# 1025-A.net
KiCad netlist of a schematic drawn in Altium Designer
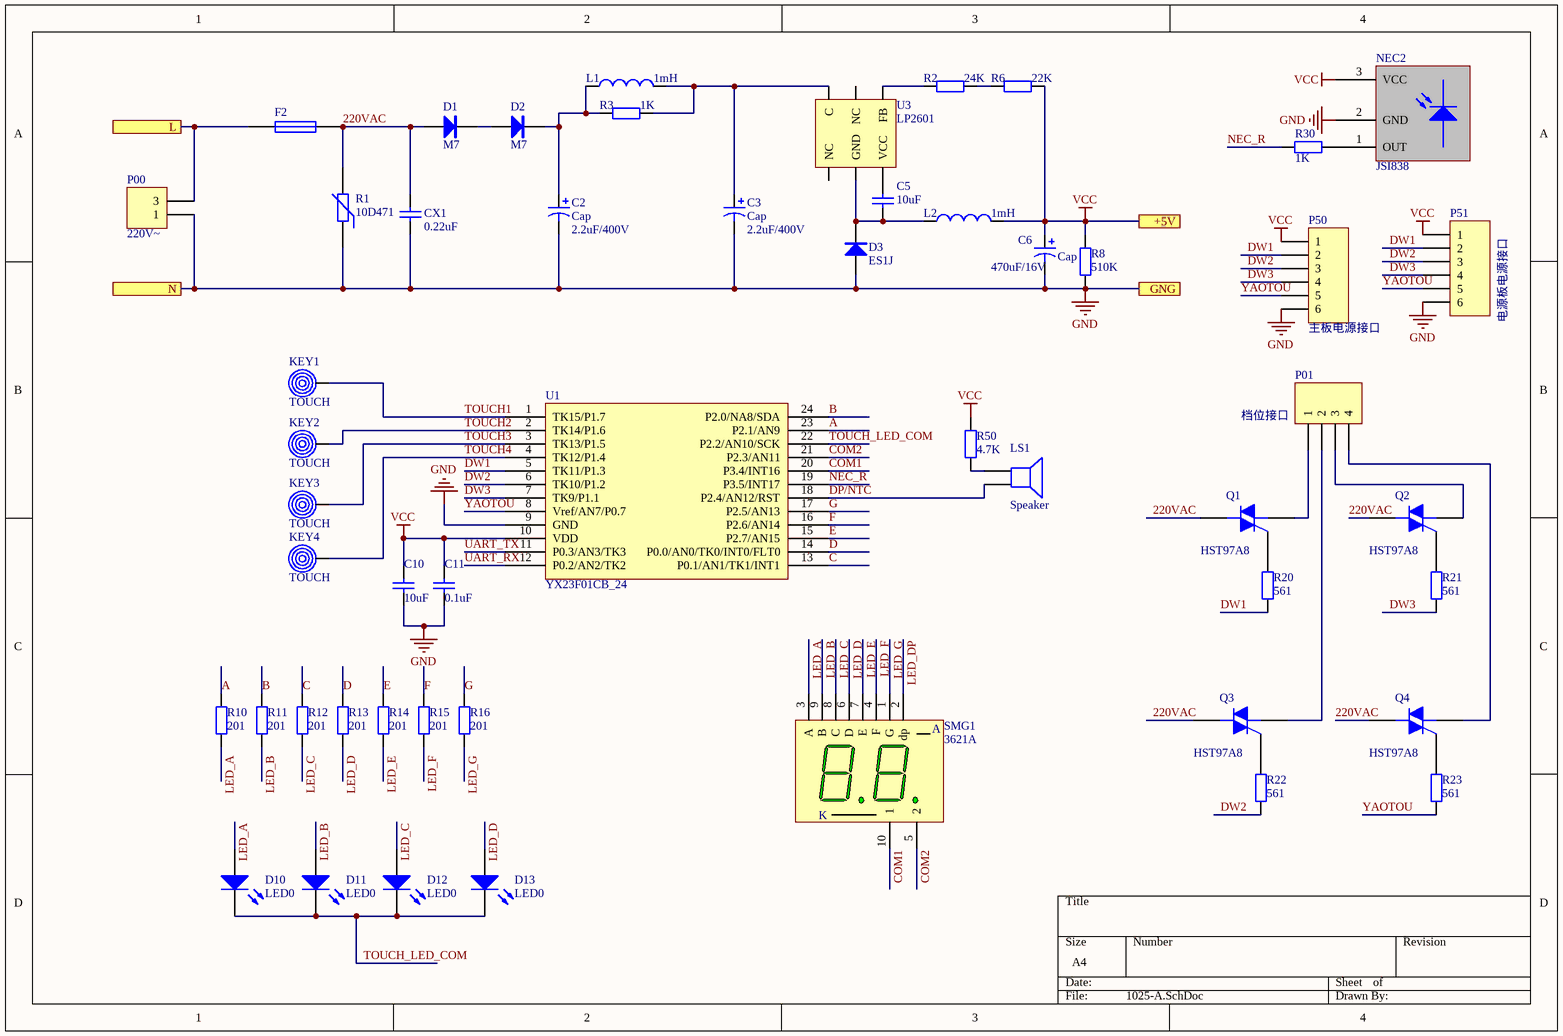
[diagram p0: 1025-A.SchDoc]

(export (version "E")
  (design (tool "Eeschema 10.0.6"))
  (components
    (comp (ref "C2")
      (value "Cap")
      (footprint "CAE8-3.05")
      (description "Polarized Capacitor (Radial)")
      (fields (field (name "ALTIUM_VALUE") "2.2uF/400V") (field (name "PUBLISHER") "Altium Limited"))
      (libsource (lib "Miscellaneous Devices") (part "Cap Pol1"))
    )
    (comp (ref "C3")
      (value "Cap")
      (footprint "CAE8-3.05")
      (description "Polarized Capacitor (Radial)")
      (fields (field (name "ALTIUM_VALUE") "2.2uF/400V") (field (name "PUBLISHER") "Altium Limited"))
      (libsource (lib "Miscellaneous Devices") (part "Cap Pol1"))
    )
    (comp (ref "C5")
      (value "10uF")
      (footprint "C 1206_M")
      (description "Capacitor")
      (fields (field (name "Comment") "Cap") (field (name "PUBLISHER") "Altium Limited"))
      (libsource (lib "Miscellaneous Devices") (part "Cap"))
    )
    (comp (ref "C6")
      (value "Cap")
      (footprint "CAE8-3.05")
      (description "Polarized Capacitor (Radial)")
      (fields (field (name "ALTIUM_VALUE") "470uF/16V") (field (name "PUBLISHER") "Altium Limited"))
      (libsource (lib "Miscellaneous Devices") (part "Cap Pol1"))
    )
    (comp (ref "C10")
      (value "10uF")
      (footprint "C 0805_L")
      (description "Capacitor")
      (fields (field (name "Comment") "Cap") (field (name "PUBLISHER") "Altium Limited"))
      (libsource (lib "Miscellaneous Devices") (part "Cap"))
    )
    (comp (ref "C11")
      (value "0.1uF")
      (footprint "C 0603_L")
      (description "Capacitor")
      (fields (field (name "Comment") "Cap") (field (name "PUBLISHER") "Altium Limited"))
      (libsource (lib "Miscellaneous Devices") (part "Cap"))
    )
    (comp (ref "CX1")
      (value "0.22uF")
      (footprint "CX2-13*5-10")
      (description "安规Capacitor")
      (fields (field (name "Comment") "安规电容") (field (name "PUBLISHER") "Altium Limited"))
      (libsource (lib "Miscellaneous Devices") (part "Cap"))
    )
    (comp (ref "D1")
      (value "M7")
      (footprint "D3528")
      (description "整流二极管")
      (fields (field (name "版权归属") "封装库来自淘宝 ID：黄晶宝石"))
      (libsource (lib "二极管-整流桥") (part "M7"))
    )
    (comp (ref "D2")
      (value "M7")
      (footprint "D3528")
      (description "整流二极管")
      (fields (field (name "版权归属") "封装库来自淘宝 ID：黄晶宝石"))
      (libsource (lib "二极管-整流桥") (part "M7"))
    )
    (comp (ref "D3")
      (value "ES1J")
      (footprint "D3528")
      (description "快速二极管")
      (fields (field (name "版权归属") "封装库来自淘宝 ID：黄晶宝石"))
      (libsource (lib "二极管-整流桥") (part "M7"))
    )
    (comp (ref "D10")
      (value "LED0")
      (footprint "LED 0805W")
      (description "Typical INFRARED GaAs LED")
      (fields (field (name "PUBLISHER") "Altium Limited"))
      (libsource (lib "Miscellaneous Devices") (part "LED0"))
    )
    (comp (ref "D11")
      (value "LED0")
      (footprint "LED 0805W")
      (description "Typical INFRARED GaAs LED")
      (fields (field (name "PUBLISHER") "Altium Limited"))
      (libsource (lib "Miscellaneous Devices") (part "LED0"))
    )
    (comp (ref "D12")
      (value "LED0")
      (footprint "LED 0805W")
      (description "Typical INFRARED GaAs LED")
      (fields (field (name "PUBLISHER") "Altium Limited"))
      (libsource (lib "Miscellaneous Devices") (part "LED0"))
    )
    (comp (ref "D13")
      (value "LED0")
      (footprint "LED 0805W")
      (description "Typical INFRARED GaAs LED")
      (fields (field (name "PUBLISHER") "Altium Limited"))
      (libsource (lib "Miscellaneous Devices") (part "LED0"))
    )
    (comp (ref "F2")
      (value "Fuse 1")
      (footprint "FUSE5.08")
      (description "Fuse")
      (fields (field (name "PUBLISHER") "Altium Limited"))
      (libsource (lib "Miscellaneous Devices") (part "Fuse 1"))
    )
    (comp (ref "KEY1")
      (value "TOUCH")
      (footprint "KEY-T9-2")
      (description "触摸弹簧")
      (libsource (lib "1025") (part "TOUCH"))
    )
    (comp (ref "KEY2")
      (value "TOUCH")
      (footprint "KEY-T9-2")
      (description "触摸弹簧")
      (libsource (lib "1025") (part "TOUCH"))
    )
    (comp (ref "KEY3")
      (value "TOUCH")
      (footprint "KEY-T9-2")
      (description "触摸弹簧")
      (libsource (lib "1025") (part "TOUCH"))
    )
    (comp (ref "KEY4")
      (value "TOUCH")
      (footprint "KEY-T9-2")
      (description "触摸弹簧")
      (libsource (lib "1025") (part "TOUCH"))
    )
    (comp (ref "L1")
      (value "1mH")
      (footprint "L15_2")
      (description "Inductor")
      (fields (field (name "PUBLISHER") "Altium Limited"))
      (libsource (lib "Miscellaneous Devices") (part "Inductor"))
    )
    (comp (ref "L2")
      (value "1mH")
      (footprint "L3")
      (description "Inductor")
      (fields (field (name "PUBLISHER") "Altium Limited"))
      (libsource (lib "Miscellaneous Devices") (part "Inductor"))
    )
    (comp (ref "LS1")
      (value "Speaker")
      (footprint "BEEP 4x9x5.5")
      (description "Loudspeaker")
      (fields (field (name "PUBLISHER") "Altium Limited"))
      (libsource (lib "Miscellaneous Devices") (part "Speaker"))
    )
    (comp (ref "NEC2")
      (value "JSI838")
      (footprint "HS0038B")
      (description "红外接收器")
      (libsource (lib "传感元件") (part "HS0038"))
    )
    (comp (ref "P00")
      (value "220V~")
      (footprint "VH-3AW")
      (description "Header, 2-Pin")
      (fields (field (name "PUBLISHER") "Altium Limited"))
      (libsource (lib "Miscellaneous Connectors") (part "Header 2"))
    )
    (comp (ref "P01")
      (value "档位接口")
      (footprint "XH-4AW")
      (description "Header, 4-Pin")
      (fields (field (name "PUBLISHER") "Altium Limited"))
      (libsource (lib "Miscellaneous Connectors") (part "Header 4"))
    )
    (comp (ref "P50")
      (value "主板电源接口")
      (footprint "HDR2.54-LI-6P")
      (description "Header, 6-Pin")
      (fields (field (name "PUBLISHER") "Altium Limited"))
      (libsource (lib "Miscellaneous Connectors") (part "Header 6"))
    )
    (comp (ref "P51")
      (value "电源板电源接口")
      (footprint "HDR2.54-LI-6P")
      (description "Header, 6-Pin")
      (fields (field (name "PUBLISHER") "Altium Limited"))
      (libsource (lib "Miscellaneous Connectors") (part "Header 6"))
    )
    (comp (ref "Q1")
      (value "HST97A8")
      (footprint "SOT-89")
      (description "Silicon Bidirectional Triode Thyristor")
      (fields (field (name "PUBLISHER") "Altium Limited"))
      (libsource (lib "Miscellaneous Devices") (part "Triac"))
    )
    (comp (ref "Q2")
      (value "HST97A8")
      (footprint "SOT-89")
      (description "Silicon Bidirectional Triode Thyristor")
      (fields (field (name "PUBLISHER") "Altium Limited"))
      (libsource (lib "Miscellaneous Devices") (part "Triac"))
    )
    (comp (ref "Q3")
      (value "HST97A8")
      (footprint "SOT-89")
      (description "Silicon Bidirectional Triode Thyristor")
      (fields (field (name "PUBLISHER") "Altium Limited"))
      (libsource (lib "Miscellaneous Devices") (part "Triac"))
    )
    (comp (ref "Q4")
      (value "HST97A8")
      (footprint "SOT-89")
      (description "Silicon Bidirectional Triode Thyristor")
      (fields (field (name "PUBLISHER") "Altium Limited"))
      (libsource (lib "Miscellaneous Devices") (part "Triac"))
    )
    (comp (ref "R1")
      (value "10D471")
      (footprint "ZNR7.5")
      (description "Varistor (Voltage-Sensitive Resistor)")
      (fields (field (name "PUBLISHER") "Altium Limited"))
      (libsource (lib "Miscellaneous Devices") (part "Res Varistor"))
    )
    (comp (ref "R2")
      (value "24K")
      (footprint "R 1206-HP_M")
      (description "Resistor")
      (fields (field (name "Comment") "Res2") (field (name "PUBLISHER") "Altium Limited"))
      (libsource (lib "") (part "Res2_1"))
    )
    (comp (ref "R3")
      (value "1K")
      (footprint "R 1206-HP_M")
      (description "Resistor")
      (fields (field (name "Comment") "Res2") (field (name "PUBLISHER") "Altium Limited"))
      (libsource (lib "") (part "Res2_1"))
    )
    (comp (ref "R6")
      (value "22K")
      (footprint "R 1206-HP_M")
      (description "Resistor")
      (fields (field (name "Comment") "Res2") (field (name "PUBLISHER") "Altium Limited"))
      (libsource (lib "") (part "Res2_1"))
    )
    (comp (ref "R8")
      (value "510K")
      (footprint "R 1206-HP_M")
      (description "Resistor")
      (fields (field (name "Comment") "Res2") (field (name "PUBLISHER") "Altium Limited"))
      (libsource (lib "Miscellaneous Devices") (part "Res2"))
    )
    (comp (ref "R10")
      (value "201")
      (footprint "R 0603_L")
      (description "Resistor")
      (fields (field (name "Comment") "Res2") (field (name "PUBLISHER") "Altium Limited"))
      (libsource (lib "Miscellaneous Devices") (part "Res2"))
    )
    (comp (ref "R11")
      (value "201")
      (footprint "R 0603_L")
      (description "Resistor")
      (fields (field (name "Comment") "Res2") (field (name "PUBLISHER") "Altium Limited"))
      (libsource (lib "Miscellaneous Devices") (part "Res2"))
    )
    (comp (ref "R12")
      (value "201")
      (footprint "R 0603_L")
      (description "Resistor")
      (fields (field (name "Comment") "Res2") (field (name "PUBLISHER") "Altium Limited"))
      (libsource (lib "Miscellaneous Devices") (part "Res2"))
    )
    (comp (ref "R13")
      (value "201")
      (footprint "R 0603_L")
      (description "Resistor")
      (fields (field (name "Comment") "Res2") (field (name "PUBLISHER") "Altium Limited"))
      (libsource (lib "Miscellaneous Devices") (part "Res2"))
    )
    (comp (ref "R14")
      (value "201")
      (footprint "R 0603_L")
      (description "Resistor")
      (fields (field (name "Comment") "Res2") (field (name "PUBLISHER") "Altium Limited"))
      (libsource (lib "Miscellaneous Devices") (part "Res2"))
    )
    (comp (ref "R15")
      (value "201")
      (footprint "R 0603_L")
      (description "Resistor")
      (fields (field (name "Comment") "Res2") (field (name "PUBLISHER") "Altium Limited"))
      (libsource (lib "Miscellaneous Devices") (part "Res2"))
    )
    (comp (ref "R16")
      (value "201")
      (footprint "R 0603_L")
      (description "Resistor")
      (fields (field (name "Comment") "Res2") (field (name "PUBLISHER") "Altium Limited"))
      (libsource (lib "Miscellaneous Devices") (part "Res2"))
    )
    (comp (ref "R20")
      (value "561")
      (footprint "R 1206-HP_M")
      (description "Resistor")
      (fields (field (name "Comment") "Res2") (field (name "PUBLISHER") "Altium Limited"))
      (libsource (lib "Miscellaneous Devices") (part "Res2"))
    )
    (comp (ref "R21")
      (value "561")
      (footprint "R 1206-HP_M")
      (description "Resistor")
      (fields (field (name "Comment") "Res2") (field (name "PUBLISHER") "Altium Limited"))
      (libsource (lib "Miscellaneous Devices") (part "Res2"))
    )
    (comp (ref "R22")
      (value "561")
      (footprint "R 1206-HP_M")
      (description "Resistor")
      (fields (field (name "Comment") "Res2") (field (name "PUBLISHER") "Altium Limited"))
      (libsource (lib "Miscellaneous Devices") (part "Res2"))
    )
    (comp (ref "R23")
      (value "561")
      (footprint "R 1206-HP_M")
      (description "Resistor")
      (fields (field (name "Comment") "Res2") (field (name "PUBLISHER") "Altium Limited"))
      (libsource (lib "Miscellaneous Devices") (part "Res2"))
    )
    (comp (ref "R30")
      (value "1K")
      (footprint "R 0603_L")
      (description "Resistor")
      (fields (field (name "Comment") "Res2") (field (name "PUBLISHER") "Altium Limited"))
      (libsource (lib "") (part "Res2_2"))
    )
    (comp (ref "R50")
      (value "4.7K")
      (footprint "R 0603_L")
      (description "Resistor")
      (fields (field (name "Comment") "Res2") (field (name "PUBLISHER") "Altium Limited"))
      (libsource (lib "Miscellaneous Devices") (part "Res2"))
    )
    (comp (ref "SMG1")
      (value "3621A")
      (footprint "SMG 0.36-2P")
      (description "0.36寸2位共阴数码管")
      (fields (field (name "版权归属") "封装库来自淘宝 ID：黄晶宝石"))
      (libsource (lib "数码管-TFT-OLED屏") (part "3621A"))
    )
    (comp (ref "U1")
      (value "YX23F01CB_24")
      (footprint "SOP24_M")
      (description "主控MCU")
      (libsource (lib "1025") (part "YX23F01CB_24"))
    )
    (comp (ref "U3") (value "LP2601") (libsource (lib "1025") (part "LP2601")))
  )
  (nets
    (net (code "1") (name "/220VAC") (class "Default")
      (node (ref "CX1") (pin "2") (pinfunction "2_2") (pintype "passive"))
      (node (ref "D1") (pin "A") (pinfunction "A_A") (pintype "passive"))
      (node (ref "F2") (pin "2") (pinfunction "2_2") (pintype "passive"))
      (node (ref "Q1") (pin "2") (pinfunction "T2_2") (pintype "passive"))
      (node (ref "Q2") (pin "2") (pinfunction "T2_2") (pintype "passive"))
      (node (ref "Q3") (pin "2") (pinfunction "T2_2") (pintype "passive"))
      (node (ref "Q4") (pin "2") (pinfunction "T2_2") (pintype "passive"))
      (node (ref "R1") (pin "2") (pinfunction "2_2") (pintype "passive"))
    )
    (net (code "2") (name "/A") (class "Default")
      (node (ref "R10") (pin "2") (pinfunction "2_2") (pintype "passive"))
      (node (ref "U1") (pin "23") (pinfunction "P2.1/AN9_23") (pintype "open_collector"))
    )
    (net (code "3") (name "/B") (class "Default")
      (node (ref "R11") (pin "2") (pinfunction "2_2") (pintype "passive"))
      (node (ref "U1") (pin "24") (pinfunction "P2.0/NA8/SDA_24") (pintype "open_collector"))
    )
    (net (code "4") (name "/C") (class "Default")
      (node (ref "R12") (pin "2") (pinfunction "2_2") (pintype "passive"))
      (node (ref "U1") (pin "13") (pinfunction "P0.1/AN1/TK1/INT1_13") (pintype "open_collector"))
    )
    (net (code "5") (name "/COM1") (class "Default")
      (node (ref "SMG1") (pin "10") (pinfunction "1_10") (pintype "passive"))
      (node (ref "U1") (pin "20") (pinfunction "P3.4/INT16_20") (pintype "open_collector"))
    )
    (net (code "6") (name "/COM2") (class "Default")
      (node (ref "SMG1") (pin "5") (pinfunction "2_5") (pintype "passive"))
      (node (ref "U1") (pin "21") (pinfunction "P2.3/AN11_21") (pintype "open_collector"))
    )
    (net (code "7") (name "/D") (class "Default")
      (node (ref "R13") (pin "2") (pinfunction "2_2") (pintype "passive"))
      (node (ref "U1") (pin "14") (pinfunction "P0.0/AN0/TK0/INT0/FLT0_14") (pintype "open_collector"))
    )
    (net (code "8") (name "/DP{slash}NTC") (class "Default")
      (node (ref "LS1") (pin "2") (pinfunction "2_2") (pintype "passive"))
      (node (ref "U1") (pin "18") (pinfunction "P2.4/AN12/RST_18") (pintype "open_collector"))
    )
    (net (code "9") (name "/DW1") (class "Default")
      (node (ref "P50") (pin "2") (pinfunction "2_2") (pintype "passive"))
      (node (ref "P51") (pin "2") (pinfunction "2_2") (pintype "passive"))
      (node (ref "R20") (pin "1") (pinfunction "1_1") (pintype "passive"))
      (node (ref "U1") (pin "5") (pinfunction "TK11/P1.3_5") (pintype "open_collector"))
    )
    (net (code "10") (name "/DW2") (class "Default")
      (node (ref "P50") (pin "3") (pinfunction "3_3") (pintype "passive"))
      (node (ref "P51") (pin "3") (pinfunction "3_3") (pintype "passive"))
      (node (ref "R22") (pin "1") (pinfunction "1_1") (pintype "passive"))
      (node (ref "U1") (pin "6") (pinfunction "TK10/P1.2_6") (pintype "open_collector"))
    )
    (net (code "11") (name "/DW3") (class "Default")
      (node (ref "P50") (pin "4") (pinfunction "4_4") (pintype "passive"))
      (node (ref "P51") (pin "4") (pinfunction "4_4") (pintype "passive"))
      (node (ref "R21") (pin "1") (pinfunction "1_1") (pintype "passive"))
      (node (ref "U1") (pin "7") (pinfunction "TK9/P1.1_7") (pintype "open_collector"))
    )
    (net (code "12") (name "/E") (class "Default")
      (node (ref "R14") (pin "2") (pinfunction "2_2") (pintype "passive"))
      (node (ref "U1") (pin "15") (pinfunction "P2.7/AN15_15") (pintype "open_collector"))
    )
    (net (code "13") (name "/F") (class "Default")
      (node (ref "R15") (pin "2") (pinfunction "2_2") (pintype "passive"))
      (node (ref "U1") (pin "16") (pinfunction "P2.6/AN14_16") (pintype "open_collector"))
    )
    (net (code "14") (name "/G") (class "Default")
      (node (ref "R16") (pin "2") (pinfunction "2_2") (pintype "passive"))
      (node (ref "U1") (pin "17") (pinfunction "P2.5/AN13_17") (pintype "open_collector"))
    )
    (net (code "15") (name "/L") (class "Default")
      (node (ref "F2") (pin "1") (pinfunction "1_1") (pintype "passive"))
      (node (ref "P00") (pin "3") (pinfunction "3_3") (pintype "passive"))
    )
    (net (code "16") (name "/LED_A") (class "Default")
      (node (ref "D10") (pin "1") (pinfunction "A_1") (pintype "passive"))
      (node (ref "R10") (pin "1") (pinfunction "1_1") (pintype "passive"))
      (node (ref "SMG1") (pin "3") (pinfunction "A_3") (pintype "passive"))
    )
    (net (code "17") (name "/LED_B") (class "Default")
      (node (ref "D11") (pin "1") (pinfunction "A_1") (pintype "passive"))
      (node (ref "R11") (pin "1") (pinfunction "1_1") (pintype "passive"))
      (node (ref "SMG1") (pin "9") (pinfunction "B_9") (pintype "passive"))
    )
    (net (code "18") (name "/LED_C") (class "Default")
      (node (ref "D12") (pin "1") (pinfunction "A_1") (pintype "passive"))
      (node (ref "R12") (pin "1") (pinfunction "1_1") (pintype "passive"))
      (node (ref "SMG1") (pin "8") (pinfunction "C_8") (pintype "passive"))
    )
    (net (code "19") (name "/LED_D") (class "Default")
      (node (ref "D13") (pin "1") (pinfunction "A_1") (pintype "passive"))
      (node (ref "R13") (pin "1") (pinfunction "1_1") (pintype "passive"))
      (node (ref "SMG1") (pin "6") (pinfunction "D_6") (pintype "passive"))
    )
    (net (code "20") (name "/LED_DP") (class "Default")
      (node (ref "SMG1") (pin "2") (pinfunction "dp_2") (pintype "passive"))
    )
    (net (code "21") (name "/LED_E") (class "Default")
      (node (ref "R14") (pin "1") (pinfunction "1_1") (pintype "passive"))
      (node (ref "SMG1") (pin "7") (pinfunction "E_7") (pintype "passive"))
    )
    (net (code "22") (name "/LED_F") (class "Default")
      (node (ref "R15") (pin "1") (pinfunction "1_1") (pintype "passive"))
      (node (ref "SMG1") (pin "4") (pinfunction "F_4") (pintype "passive"))
    )
    (net (code "23") (name "/LED_G") (class "Default")
      (node (ref "R16") (pin "1") (pinfunction "1_1") (pintype "passive"))
      (node (ref "SMG1") (pin "1") (pinfunction "G_1") (pintype "passive"))
    )
    (net (code "24") (name "/NEC_R") (class "Default")
      (node (ref "R30") (pin "2") (pinfunction "2_2") (pintype "passive"))
      (node (ref "U1") (pin "19") (pinfunction "P3.5/INT17_19") (pintype "open_collector"))
    )
    (net (code "25") (name "/TOUCH1") (class "Default")
      (node (ref "KEY1") (pin "1") (pinfunction "1_1") (pintype "passive"))
      (node (ref "U1") (pin "1") (pinfunction "TK15/P1.7_1") (pintype "open_collector"))
    )
    (net (code "26") (name "/TOUCH2") (class "Default")
      (node (ref "KEY2") (pin "1") (pinfunction "1_1") (pintype "passive"))
      (node (ref "U1") (pin "2") (pinfunction "TK14/P1.6_2") (pintype "open_collector"))
    )
    (net (code "27") (name "/TOUCH3") (class "Default")
      (node (ref "KEY3") (pin "1") (pinfunction "1_1") (pintype "passive"))
      (node (ref "U1") (pin "3") (pinfunction "TK13/P1.5_3") (pintype "open_collector"))
    )
    (net (code "28") (name "/TOUCH4") (class "Default")
      (node (ref "KEY4") (pin "1") (pinfunction "1_1") (pintype "passive"))
      (node (ref "U1") (pin "4") (pinfunction "TK12/P1.4_4") (pintype "open_collector"))
    )
    (net (code "29") (name "/TOUCH_LED_COM") (class "Default")
      (node (ref "D10") (pin "2") (pinfunction "K_2") (pintype "passive"))
      (node (ref "D11") (pin "2") (pinfunction "K_2") (pintype "passive"))
      (node (ref "D12") (pin "2") (pinfunction "K_2") (pintype "passive"))
      (node (ref "D13") (pin "2") (pinfunction "K_2") (pintype "passive"))
      (node (ref "U1") (pin "22") (pinfunction "P2.2/AN10/SCK_22") (pintype "open_collector"))
    )
    (net (code "30") (name "/UART_RX") (class "Default")
      (node (ref "U1") (pin "12") (pinfunction "P0.2/AN2/TK2_12") (pintype "open_collector"))
    )
    (net (code "31") (name "/UART_TX") (class "Default")
      (node (ref "U1") (pin "11") (pinfunction "P0.3/AN3/TK3_11") (pintype "open_collector"))
    )
    (net (code "32") (name "/YAOTOU") (class "Default")
      (node (ref "P50") (pin "5") (pinfunction "5_5") (pintype "passive"))
      (node (ref "P51") (pin "5") (pinfunction "5_5") (pintype "passive"))
      (node (ref "R23") (pin "1") (pinfunction "1_1") (pintype "passive"))
      (node (ref "U1") (pin "8") (pinfunction "Vref/AN7/P0.7_8") (pintype "open_collector"))
    )
    (net (code "33") (name "GND") (class "Default")
      (node (ref "C10") (pin "1") (pinfunction "1_1") (pintype "passive"))
      (node (ref "C11") (pin "1") (pinfunction "1_1") (pintype "passive"))
      (node (ref "C2") (pin "2") (pinfunction "2_2") (pintype "passive"))
      (node (ref "C3") (pin "2") (pinfunction "2_2") (pintype "passive"))
      (node (ref "C6") (pin "2") (pinfunction "2_2") (pintype "passive"))
      (node (ref "CX1") (pin "1") (pinfunction "1_1") (pintype "passive"))
      (node (ref "D3") (pin "A") (pinfunction "A_A") (pintype "passive"))
      (node (ref "NEC2") (pin "2") (pinfunction "GND_2") (pintype "passive"))
      (node (ref "P00") (pin "1") (pinfunction "1_1") (pintype "passive"))
      (node (ref "P50") (pin "6") (pinfunction "6_6") (pintype "passive"))
      (node (ref "P51") (pin "6") (pinfunction "6_6") (pintype "passive"))
      (node (ref "R1") (pin "1") (pinfunction "1_1") (pintype "passive"))
      (node (ref "R8") (pin "1") (pinfunction "1_1") (pintype "passive"))
      (node (ref "U1") (pin "9") (pinfunction "GND_9") (pintype "power_in"))
    )
    (net (code "34") (name "Net-(C2-Pad1)") (class "Default")
      (node (ref "C2") (pin "1") (pinfunction "1_1") (pintype "passive"))
      (node (ref "D2") (pin "K") (pinfunction "K_K") (pintype "passive"))
      (node (ref "L1") (pin "1") (pinfunction "1_1") (pintype "passive"))
      (node (ref "R3") (pin "1") (pinfunction "1_1") (pintype "passive"))
    )
    (net (code "35") (name "Net-(D1-PadK)") (class "Default")
      (node (ref "D1") (pin "K") (pinfunction "K_K") (pintype "passive"))
      (node (ref "D2") (pin "A") (pinfunction "A_A") (pintype "passive"))
    )
    (net (code "36") (name "Net-(LS1-Pad1)") (class "Default")
      (node (ref "LS1") (pin "1") (pinfunction "1_1") (pintype "passive"))
      (node (ref "R50") (pin "1") (pinfunction "1_1") (pintype "passive"))
    )
    (net (code "37") (name "Net-(NEC2-OUT)") (class "Default")
      (node (ref "NEC2") (pin "1") (pinfunction "OUT_1") (pintype "passive"))
      (node (ref "R30") (pin "1") (pinfunction "1_1") (pintype "passive"))
    )
    (net (code "38") (name "Net-(Q1-G)") (class "Default")
      (node (ref "Q1") (pin "3") (pinfunction "G_3") (pintype "passive"))
      (node (ref "R20") (pin "2") (pinfunction "2_2") (pintype "passive"))
    )
    (net (code "39") (name "Net-(Q1-T1)") (class "Default")
      (node (ref "P01") (pin "1") (pinfunction "1_1") (pintype "passive"))
      (node (ref "Q1") (pin "1") (pinfunction "T1_1") (pintype "passive"))
    )
    (net (code "40") (name "Net-(Q2-G)") (class "Default")
      (node (ref "Q2") (pin "3") (pinfunction "G_3") (pintype "passive"))
      (node (ref "R21") (pin "2") (pinfunction "2_2") (pintype "passive"))
    )
    (net (code "41") (name "Net-(Q2-T1)") (class "Default")
      (node (ref "P01") (pin "3") (pinfunction "3_3") (pintype "passive"))
      (node (ref "Q2") (pin "1") (pinfunction "T1_1") (pintype "passive"))
    )
    (net (code "42") (name "Net-(Q3-G)") (class "Default")
      (node (ref "Q3") (pin "3") (pinfunction "G_3") (pintype "passive"))
      (node (ref "R22") (pin "2") (pinfunction "2_2") (pintype "passive"))
    )
    (net (code "43") (name "Net-(Q3-T1)") (class "Default")
      (node (ref "P01") (pin "2") (pinfunction "2_2") (pintype "passive"))
      (node (ref "Q3") (pin "1") (pinfunction "T1_1") (pintype "passive"))
    )
    (net (code "44") (name "Net-(Q4-G)") (class "Default")
      (node (ref "Q4") (pin "3") (pinfunction "G_3") (pintype "passive"))
      (node (ref "R23") (pin "2") (pinfunction "2_2") (pintype "passive"))
    )
    (net (code "45") (name "Net-(Q4-T1)") (class "Default")
      (node (ref "P01") (pin "4") (pinfunction "4_4") (pintype "passive"))
      (node (ref "Q4") (pin "1") (pinfunction "T1_1") (pintype "passive"))
    )
    (net (code "46") (name "Net-(R2-Pad2)") (class "Default")
      (node (ref "R2") (pin "2") (pinfunction "2_2") (pintype "passive"))
      (node (ref "R6") (pin "1") (pinfunction "1_1") (pintype "passive"))
    )
    (net (code "47") (name "Net-(U3-C)") (class "Default")
      (node (ref "C3") (pin "1") (pinfunction "1_1") (pintype "passive"))
      (node (ref "L1") (pin "2") (pinfunction "2_2") (pintype "passive"))
      (node (ref "R3") (pin "2") (pinfunction "2_2") (pintype "passive"))
      (node (ref "U3") (pin "4") (pinfunction "C_4") (pintype "open_collector"))
    )
    (net (code "48") (name "Net-(U3-FB)") (class "Default")
      (node (ref "R2") (pin "1") (pinfunction "1_1") (pintype "passive"))
      (node (ref "U3") (pin "6") (pinfunction "FB_6") (pintype "open_collector"))
    )
    (net (code "49") (name "Net-(U3-GND)") (class "Default")
      (node (ref "C5") (pin "1") (pinfunction "1_1") (pintype "passive"))
      (node (ref "D3") (pin "K") (pinfunction "K_K") (pintype "passive"))
      (node (ref "L2") (pin "1") (pinfunction "1_1") (pintype "passive"))
      (node (ref "U3") (pin "2") (pinfunction "GND_2") (pintype "open_collector"))
    )
    (net (code "50") (name "Net-(U3-VCC)") (class "Default")
      (node (ref "C5") (pin "2") (pinfunction "2_2") (pintype "passive"))
      (node (ref "U3") (pin "1") (pinfunction "VCC_1") (pintype "open_collector"))
    )
    (net (code "51") (name "VCC") (class "Default")
      (node (ref "C10") (pin "2") (pinfunction "2_2") (pintype "passive"))
      (node (ref "C11") (pin "2") (pinfunction "2_2") (pintype "passive"))
      (node (ref "C6") (pin "1") (pinfunction "1_1") (pintype "passive"))
      (node (ref "L2") (pin "2") (pinfunction "2_2") (pintype "passive"))
      (node (ref "NEC2") (pin "3") (pinfunction "VCC_3") (pintype "passive"))
      (node (ref "P50") (pin "1") (pinfunction "1_1") (pintype "passive"))
      (node (ref "P51") (pin "1") (pinfunction "1_1") (pintype "passive"))
      (node (ref "R50") (pin "2") (pinfunction "2_2") (pintype "passive"))
      (node (ref "R6") (pin "2") (pinfunction "2_2") (pintype "passive"))
      (node (ref "R8") (pin "2") (pinfunction "2_2") (pintype "passive"))
      (node (ref "U1") (pin "10") (pinfunction "VDD_10") (pintype "power_in"))
    )
    (net (code "52") (name "unconnected-(U3-NC-Pad3)") (class "Default")
      (node (ref "U3") (pin "3") (pinfunction "NC_3") (pintype "open_collector"))
    )
    (net (code "53") (name "unconnected-(U3-NC-Pad5)") (class "Default")
      (node (ref "U3") (pin "5") (pinfunction "NC_5") (pintype "open_collector"))
    )
  )
)
